# SAS_rev03.net
KiCad netlist of a schematic drawn in EAGLE
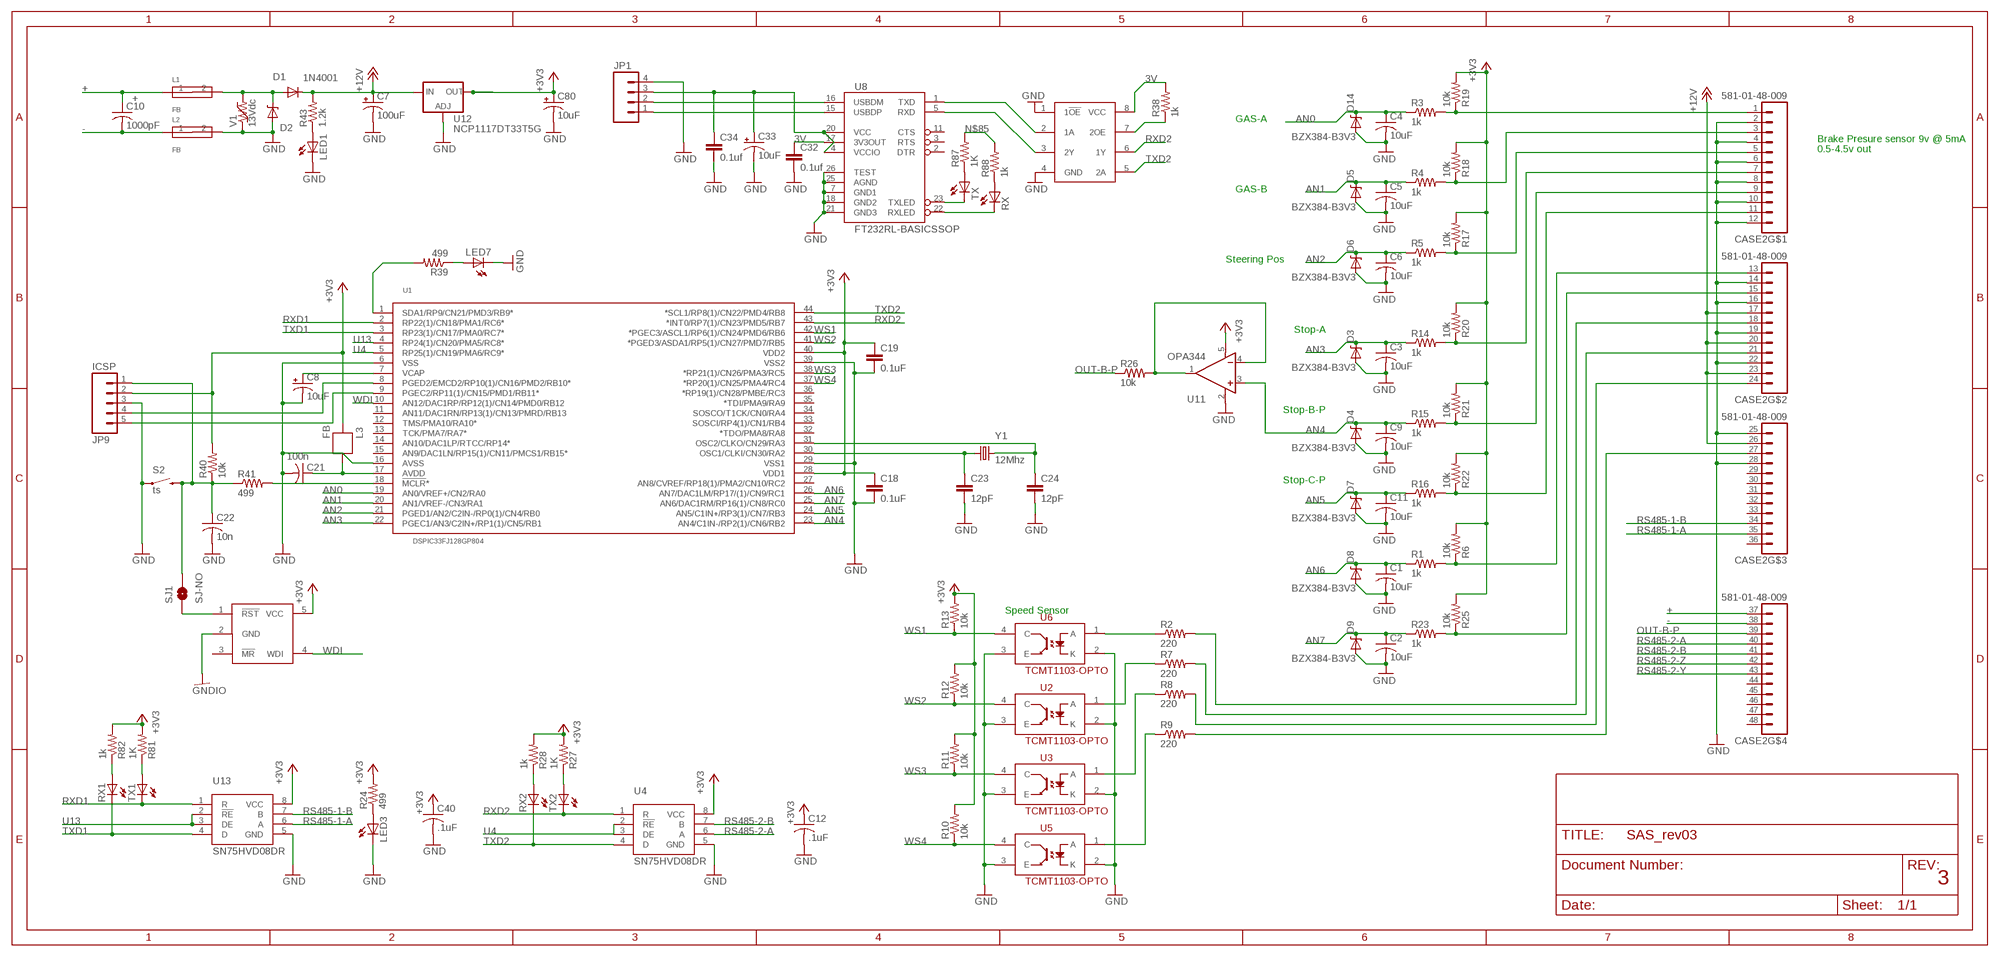
[diagram p0: schematic, sheet 1]

(export (version "E")
  (design (tool "Eeschema 10.0.6"))
  (components
    (comp (ref "C1")
      (value "10uF")
      (footprint "eagle-import:C0805")
      (libsource (lib "eagle-import") (part "C-USC0805"))
    )
    (comp (ref "C2")
      (value "10uF")
      (footprint "eagle-import:C0805")
      (libsource (lib "eagle-import") (part "C-USC0805"))
    )
    (comp (ref "C3")
      (value "10uF")
      (footprint "eagle-import:C0805")
      (libsource (lib "eagle-import") (part "C-USC0805"))
    )
    (comp (ref "C4")
      (value "10uF")
      (footprint "eagle-import:C0805")
      (libsource (lib "eagle-import") (part "C-USC0805"))
    )
    (comp (ref "C5")
      (value "10uF")
      (footprint "eagle-import:C0805")
      (libsource (lib "eagle-import") (part "C-USC0805"))
    )
    (comp (ref "C6")
      (value "10uF")
      (footprint "eagle-import:C0805")
      (libsource (lib "eagle-import") (part "C-USC0805"))
    )
    (comp (ref "C7")
      (value "100uF")
      (footprint "eagle-import:EIA7343")
      (libsource (lib "eagle-import") (part "SparkFun-Capacitors_CAP_POL7343"))
    )
    (comp (ref "C8")
      (value "10uF")
      (footprint "eagle-import:EIA3216")
      (libsource (lib "eagle-import") (part "10UF-TANT"))
    )
    (comp (ref "C9")
      (value "10uF")
      (footprint "eagle-import:C0805")
      (libsource (lib "eagle-import") (part "C-USC0805"))
    )
    (comp (ref "C10")
      (value "1000pF")
      (footprint "eagle-import:C1825")
      (libsource (lib "eagle-import") (part "C-USC1825"))
    )
    (comp (ref "C11")
      (value "10uF")
      (footprint "eagle-import:C0805")
      (libsource (lib "eagle-import") (part "C-USC0805"))
    )
    (comp (ref "C12")
      (value ".1uF")
      (footprint "eagle-import:C0805")
      (libsource (lib "eagle-import") (part "C-USC0805"))
    )
    (comp (ref "C18")
      (value "0.1uF")
      (footprint "eagle-import:0805")
      (libsource (lib "eagle-import") (part "SparkFun-Capacitors_CAP0805"))
    )
    (comp (ref "C19")
      (value "0.1uF")
      (footprint "eagle-import:0805")
      (libsource (lib "eagle-import") (part "SparkFun-Capacitors_CAP0805"))
    )
    (comp (ref "C21")
      (value "100n")
      (footprint "eagle-import:C0805")
      (libsource (lib "eagle-import") (part "C-USC0805"))
    )
    (comp (ref "C22")
      (value "10n")
      (footprint "eagle-import:C0805")
      (libsource (lib "eagle-import") (part "C-USC0805"))
    )
    (comp (ref "C23")
      (value "12pF")
      (footprint "eagle-import:0805")
      (libsource (lib "eagle-import") (part "SparkFun-Capacitors_CAP0805"))
    )
    (comp (ref "C24")
      (value "12pF")
      (footprint "eagle-import:0805")
      (libsource (lib "eagle-import") (part "SparkFun-Capacitors_CAP0805"))
    )
    (comp (ref "C32")
      (value "0.1uf")
      (footprint "eagle-import:0805")
      (libsource (lib "eagle-import") (part "CAP0805"))
    )
    (comp (ref "C33")
      (value "10uF")
      (footprint "eagle-import:EIA3216")
      (libsource (lib "eagle-import") (part "CAP_POL1206"))
    )
    (comp (ref "C34")
      (value "0.1uf")
      (footprint "eagle-import:0805")
      (libsource (lib "eagle-import") (part "CAP0805"))
    )
    (comp (ref "C40")
      (value ".1uF")
      (footprint "eagle-import:C0805")
      (libsource (lib "eagle-import") (part "C-USC0805"))
    )
    (comp (ref "C80")
      (value "10uF")
      (footprint "eagle-import:POLC1206")
      (libsource (lib "eagle-import") (part "POLCAP"))
    )
    (comp (ref "CASE2")
      (value "581-01-48-009")
      (footprint "eagle-import:581-01-48-009")
      (libsource (lib "eagle-import") (part "581-01-48-009"))
    )
    (comp (ref "D1")
      (value "1N4001")
      (footprint "eagle-import:SOD123")
      (libsource (lib "eagle-import") (part "DIODE-SOD123"))
    )
    (comp (ref "D2")
      (value "MM5Z30")
      (footprint "eagle-import:SOD-523F")
      (libsource (lib "eagle-import") (part "MM5Z30"))
    )
    (comp (ref "D3")
      (value "BZX384-B3V3")
      (footprint "eagle-import:SOD-323")
      (libsource (lib "eagle-import") (part "DIODE-ZENER-BZT52"))
    )
    (comp (ref "D4")
      (value "BZX384-B3V3")
      (footprint "eagle-import:SOD-323")
      (libsource (lib "eagle-import") (part "DIODE-ZENER-BZT52"))
    )
    (comp (ref "D5")
      (value "BZX384-B3V3")
      (footprint "eagle-import:SOD-323")
      (libsource (lib "eagle-import") (part "DIODE-ZENER-BZT52"))
    )
    (comp (ref "D6")
      (value "BZX384-B3V3")
      (footprint "eagle-import:SOD-323")
      (libsource (lib "eagle-import") (part "DIODE-ZENER-BZT52"))
    )
    (comp (ref "D7")
      (value "BZX384-B3V3")
      (footprint "eagle-import:SOD-323")
      (libsource (lib "eagle-import") (part "DIODE-ZENER-BZT52"))
    )
    (comp (ref "D8")
      (value "BZX384-B3V3")
      (footprint "eagle-import:SOD-323")
      (libsource (lib "eagle-import") (part "DIODE-ZENER-BZT52"))
    )
    (comp (ref "D9")
      (value "BZX384-B3V3")
      (footprint "eagle-import:SOD-323")
      (libsource (lib "eagle-import") (part "DIODE-ZENER-BZT52"))
    )
    (comp (ref "D14")
      (value "BZX384-B3V3")
      (footprint "eagle-import:SOD-323")
      (libsource (lib "eagle-import") (part "DIODE-ZENER-BZT52"))
    )
    (comp (ref "JP1")
      (value "M04POLAR")
      (footprint "eagle-import:MOLEX-1X4")
      (libsource (lib "eagle-import") (part "M04POLAR"))
    )
    (comp (ref "JP9")
      (value "ICSP")
      (footprint "eagle-import:1X05_LOCK_LONGPADS")
      (libsource (lib "eagle-import") (part "M05LOCK_LONGPADS"))
    )
    (comp (ref "L1")
      (value "FB")
      (footprint "eagle-import:0603")
      (libsource (lib "eagle-import") (part "FERITEBEAD"))
    )
    (comp (ref "L2")
      (value "FB")
      (footprint "eagle-import:0603")
      (libsource (lib "eagle-import") (part "FERITEBEAD"))
    )
    (comp (ref "L3")
      (value "FB")
      (footprint "eagle-import:0603")
      (libsource (lib "eagle-import") (part "FB"))
    )
    (comp (ref "LED1")
      (value "LEDCHIP-LED0805")
      (footprint "eagle-import:CHIP-LED0805")
      (libsource (lib "eagle-import") (part "LEDCHIP-LED0805"))
    )
    (comp (ref "LED3")
      (value "LEDCHIP-LED0805")
      (footprint "eagle-import:CHIP-LED0805")
      (libsource (lib "eagle-import") (part "LEDCHIP-LED0805"))
    )
    (comp (ref "LED7")
      (value "LEDCHIP-LED0805")
      (footprint "eagle-import:CHIP-LED0805")
      (libsource (lib "eagle-import") (part "LEDCHIP-LED0805"))
    )
    (comp (ref "R1")
      (value "1k")
      (footprint "eagle-import:R0805")
      (libsource (lib "eagle-import") (part "R-US_R0805"))
    )
    (comp (ref "R2")
      (value "220")
      (footprint "eagle-import:R0805")
      (libsource (lib "eagle-import") (part "R-US_R0805"))
    )
    (comp (ref "R3")
      (value "1k")
      (footprint "eagle-import:R0805")
      (libsource (lib "eagle-import") (part "R-US_R0805"))
    )
    (comp (ref "R4")
      (value "1k")
      (footprint "eagle-import:R0805")
      (libsource (lib "eagle-import") (part "R-US_R0805"))
    )
    (comp (ref "R5")
      (value "1k")
      (footprint "eagle-import:R0805")
      (libsource (lib "eagle-import") (part "R-US_R0805"))
    )
    (comp (ref "R6")
      (value "10k")
      (footprint "eagle-import:R0805")
      (libsource (lib "eagle-import") (part "R-US_R0805"))
    )
    (comp (ref "R7")
      (value "220")
      (footprint "eagle-import:R0805")
      (libsource (lib "eagle-import") (part "R-US_R0805"))
    )
    (comp (ref "R8")
      (value "220")
      (footprint "eagle-import:R0805")
      (libsource (lib "eagle-import") (part "R-US_R0805"))
    )
    (comp (ref "R9")
      (value "220")
      (footprint "eagle-import:R0805")
      (libsource (lib "eagle-import") (part "R-US_R0805"))
    )
    (comp (ref "R10")
      (value "10k")
      (footprint "eagle-import:R0805")
      (libsource (lib "eagle-import") (part "R-US_R0805"))
    )
    (comp (ref "R11")
      (value "10k")
      (footprint "eagle-import:R0805")
      (libsource (lib "eagle-import") (part "R-US_R0805"))
    )
    (comp (ref "R12")
      (value "10k")
      (footprint "eagle-import:R0805")
      (libsource (lib "eagle-import") (part "R-US_R0805"))
    )
    (comp (ref "R13")
      (value "10k")
      (footprint "eagle-import:R0805")
      (libsource (lib "eagle-import") (part "R-US_R0805"))
    )
    (comp (ref "R14")
      (value "1k")
      (footprint "eagle-import:R0805")
      (libsource (lib "eagle-import") (part "R-US_R0805"))
    )
    (comp (ref "R15")
      (value "1k")
      (footprint "eagle-import:R0805")
      (libsource (lib "eagle-import") (part "R-US_R0805"))
    )
    (comp (ref "R16")
      (value "1k")
      (footprint "eagle-import:R0805")
      (libsource (lib "eagle-import") (part "R-US_R0805"))
    )
    (comp (ref "R17")
      (value "10k")
      (footprint "eagle-import:R0805")
      (libsource (lib "eagle-import") (part "R-US_R0805"))
    )
    (comp (ref "R18")
      (value "10k")
      (footprint "eagle-import:R0805")
      (libsource (lib "eagle-import") (part "R-US_R0805"))
    )
    (comp (ref "R19")
      (value "10k")
      (footprint "eagle-import:R0805")
      (libsource (lib "eagle-import") (part "R-US_R0805"))
    )
    (comp (ref "R20")
      (value "10k")
      (footprint "eagle-import:R0805")
      (libsource (lib "eagle-import") (part "R-US_R0805"))
    )
    (comp (ref "R21")
      (value "10k")
      (footprint "eagle-import:R0805")
      (libsource (lib "eagle-import") (part "R-US_R0805"))
    )
    (comp (ref "R22")
      (value "10k")
      (footprint "eagle-import:R0805")
      (libsource (lib "eagle-import") (part "R-US_R0805"))
    )
    (comp (ref "R23")
      (value "1k")
      (footprint "eagle-import:R0805")
      (libsource (lib "eagle-import") (part "R-US_R0805"))
    )
    (comp (ref "R24")
      (value "499")
      (footprint "eagle-import:R0805")
      (libsource (lib "eagle-import") (part "R-US_R0805"))
    )
    (comp (ref "R25")
      (value "10k")
      (footprint "eagle-import:R0805")
      (libsource (lib "eagle-import") (part "R-US_R0805"))
    )
    (comp (ref "R26")
      (value "10k")
      (footprint "eagle-import:R0805")
      (libsource (lib "eagle-import") (part "R-US_R0805"))
    )
    (comp (ref "R27")
      (value "1K")
      (footprint "eagle-import:R0805")
      (libsource (lib "eagle-import") (part "R-US_R0805"))
    )
    (comp (ref "R28")
      (value "1k")
      (footprint "eagle-import:R0805")
      (libsource (lib "eagle-import") (part "R-US_R0805"))
    )
    (comp (ref "R38")
      (value "1k")
      (footprint "eagle-import:R0805")
      (libsource (lib "eagle-import") (part "R-US_R0805"))
    )
    (comp (ref "R39")
      (value "499")
      (footprint "eagle-import:0805")
      (libsource (lib "eagle-import") (part "RESISTOR0805-RES"))
    )
    (comp (ref "R40")
      (value "10k")
      (footprint "eagle-import:0805")
      (libsource (lib "eagle-import") (part "RESISTOR0805-RES"))
    )
    (comp (ref "R41")
      (value "499")
      (footprint "eagle-import:0805")
      (libsource (lib "eagle-import") (part "SparkFun-Resistors_RESISTOR0805-RES"))
    )
    (comp (ref "R43")
      (value "1.2k")
      (footprint "eagle-import:R0805")
      (libsource (lib "eagle-import") (part "R-US_R0805"))
    )
    (comp (ref "R81")
      (value "1K")
      (footprint "eagle-import:R0805")
      (libsource (lib "eagle-import") (part "R-US_R0805"))
    )
    (comp (ref "R82")
      (value "1k")
      (footprint "eagle-import:R0805")
      (libsource (lib "eagle-import") (part "R-US_R0805"))
    )
    (comp (ref "R87")
      (value "1K")
      (footprint "eagle-import:R0805")
      (libsource (lib "eagle-import") (part "R-US_R0805"))
    )
    (comp (ref "R88")
      (value "1k")
      (footprint "eagle-import:R0805")
      (libsource (lib "eagle-import") (part "R-US_R0805"))
    )
    (comp (ref "RX")
      (value "LEDCHIPLED_0805")
      (footprint "eagle-import:CHIPLED_0805")
      (libsource (lib "eagle-import") (part "LEDCHIPLED_0805"))
    )
    (comp (ref "RX1")
      (value "LEDCHIPLED_0805")
      (footprint "eagle-import:CHIPLED_0805")
      (libsource (lib "eagle-import") (part "LEDCHIPLED_0805"))
    )
    (comp (ref "RX2")
      (value "LEDCHIPLED_0805")
      (footprint "eagle-import:CHIPLED_0805")
      (libsource (lib "eagle-import") (part "LEDCHIPLED_0805"))
    )
    (comp (ref "S2")
      (value "ts")
      (footprint "eagle-import:TACTILE-PTH")
      (libsource (lib "eagle-import") (part "SWITCH-MOMENTARY-2PTH"))
    )
    (comp (ref "SJ1")
      (value "SJ-NO")
      (footprint "eagle-import:SJ_2S-NO")
      (libsource (lib "eagle-import") (part "SOLDERJUMPERNO"))
    )
    (comp (ref "TX")
      (value "LEDCHIPLED_0805")
      (footprint "eagle-import:CHIPLED_0805")
      (libsource (lib "eagle-import") (part "LEDCHIPLED_0805"))
    )
    (comp (ref "TX1")
      (value "LEDCHIPLED_0805")
      (footprint "eagle-import:CHIPLED_0805")
      (libsource (lib "eagle-import") (part "LEDCHIPLED_0805"))
    )
    (comp (ref "TX2")
      (value "LEDCHIPLED_0805")
      (footprint "eagle-import:CHIPLED_0805")
      (libsource (lib "eagle-import") (part "LEDCHIPLED_0805"))
    )
    (comp (ref "U1")
      (value "DSPIC33FJ128GP804")
      (footprint "eagle-import:TQFP-44")
      (libsource (lib "eagle-import") (part "DSPIC33FJ128GP804"))
    )
    (comp (ref "U2")
      (value "TCMT1103-OPTO")
      (footprint "eagle-import:SSOP-4")
      (libsource (lib "eagle-import") (part "TCMT1103-OPTO"))
    )
    (comp (ref "U3")
      (value "TCMT1103-OPTO")
      (footprint "eagle-import:SSOP-4")
      (libsource (lib "eagle-import") (part "TCMT1103-OPTO"))
    )
    (comp (ref "U4")
      (value "SN75HVD08DR")
      (footprint "eagle-import:SO-8")
      (libsource (lib "eagle-import") (part "SN75HVD08DR"))
    )
    (comp (ref "U5")
      (value "TCMT1103-OPTO")
      (footprint "eagle-import:SSOP-4")
      (libsource (lib "eagle-import") (part "TCMT1103-OPTO"))
    )
    (comp (ref "U6")
      (value "TCMT1103-OPTO")
      (footprint "eagle-import:SSOP-4")
      (libsource (lib "eagle-import") (part "TCMT1103-OPTO"))
    )
    (comp (ref "U8")
      (value "FT232RL-BASICSSOP")
      (footprint "eagle-import:SSOP28DB")
      (libsource (lib "eagle-import") (part "FT232RL-BASICSSOP"))
    )
    (comp (ref "U9")
      (value "MAX823")
      (footprint "eagle-import:SOT23-5L")
      (libsource (lib "eagle-import") (part "MAX823"))
    )
    (comp (ref "U11")
      (value "OPA344")
      (footprint "eagle-import:SOT23-5")
      (libsource (lib "eagle-import") (part "OPA344"))
    )
    (comp (ref "U12")
      (value "NCP1117DT33T5G")
      (footprint "eagle-import:V-REG_DPACK")
      (libsource (lib "eagle-import") (part "V_REG_317DPACK"))
    )
    (comp (ref "U13")
      (value "SN75HVD08DR")
      (footprint "eagle-import:SO-8")
      (libsource (lib "eagle-import") (part "SN75HVD08DR"))
    )
    (comp (ref "U14")
      (value "SN74LVC2G241DCTR")
      (footprint "eagle-import:VFSOP-8")
      (libsource (lib "eagle-import") (part "SN74LVC2G241DCTR"))
    )
    (comp (ref "V1")
      (value "13Vdc")
      (footprint "eagle-import:0603")
      (libsource (lib "eagle-import") (part "VAR-RES"))
    )
    (comp (ref "Y1")
      (value "12Mhz")
      (footprint "eagle-import:CRYSTAL-SMD-5X3")
      (libsource (lib "eagle-import") (part "CRYSTAL5X3"))
    )
  )
  (nets
    (net (code "1") (name "+3V3") (class "Default")
      (node (ref "C12") (pin "1") (pinfunction "1_1") (pintype "passive"))
      (node (ref "C18") (pin "1") (pinfunction "1_1") (pintype "passive"))
      (node (ref "C19") (pin "1") (pinfunction "1_1") (pintype "passive"))
      (node (ref "C40") (pin "1") (pinfunction "1_1") (pintype "passive"))
      (node (ref "C80") (pin "1") (pinfunction "+_1") (pintype "passive"))
      (node (ref "JP9") (pin "2") (pinfunction "2_2") (pintype "passive"))
      (node (ref "L3") (pin "2") (pinfunction "P$2_2") (pintype "bidirectional"))
      (node (ref "R10") (pin "2") (pinfunction "2_2") (pintype "passive"))
      (node (ref "R11") (pin "2") (pinfunction "2_2") (pintype "passive"))
      (node (ref "R12") (pin "2") (pinfunction "2_2") (pintype "passive"))
      (node (ref "R13") (pin "2") (pinfunction "2_2") (pintype "passive"))
      (node (ref "R17") (pin "2") (pinfunction "2_2") (pintype "passive"))
      (node (ref "R18") (pin "2") (pinfunction "2_2") (pintype "passive"))
      (node (ref "R19") (pin "2") (pinfunction "2_2") (pintype "passive"))
      (node (ref "R20") (pin "2") (pinfunction "2_2") (pintype "passive"))
      (node (ref "R21") (pin "2") (pinfunction "2_2") (pintype "passive"))
      (node (ref "R22") (pin "2") (pinfunction "2_2") (pintype "passive"))
      (node (ref "R24") (pin "2") (pinfunction "2_2") (pintype "passive"))
      (node (ref "R25") (pin "2") (pinfunction "2_2") (pintype "passive"))
      (node (ref "R27") (pin "2") (pinfunction "2_2") (pintype "passive"))
      (node (ref "R28") (pin "2") (pinfunction "2_2") (pintype "passive"))
      (node (ref "R40") (pin "2") (pinfunction "2_2") (pintype "passive"))
      (node (ref "R6") (pin "2") (pinfunction "2_2") (pintype "passive"))
      (node (ref "R81") (pin "2") (pinfunction "2_2") (pintype "passive"))
      (node (ref "R82") (pin "2") (pinfunction "2_2") (pintype "passive"))
      (node (ref "U1") (pin "28") (pinfunction "VDD1_28") (pintype "bidirectional"))
      (node (ref "U1") (pin "40") (pinfunction "VDD2_40") (pintype "bidirectional"))
      (node (ref "U11") (pin "5") (pinfunction "V+_5") (pintype "power_in"))
      (node (ref "U12") (pin "4") (pinfunction "OUT_4") (pintype "output"))
      (node (ref "U13") (pin "8") (pinfunction "VCC_8") (pintype "bidirectional"))
      (node (ref "U4") (pin "8") (pinfunction "VCC_8") (pintype "bidirectional"))
      (node (ref "U9") (pin "5") (pinfunction "VCC_5") (pintype "bidirectional"))
    )
    (net (code "2") (name "+12V") (class "Default")
      (node (ref "C7") (pin "A") (pinfunction "+_A") (pintype "passive"))
      (node (ref "CASE2") (pin "17") (pinfunction "5_17") (pintype "passive"))
      (node (ref "CASE2") (pin "20") (pinfunction "8_20") (pintype "passive"))
      (node (ref "CASE2") (pin "23") (pinfunction "11_23") (pintype "passive"))
      (node (ref "CASE2") (pin "26") (pinfunction "2_26") (pintype "passive"))
      (node (ref "D1") (pin "C") (pinfunction "C_C") (pintype "passive"))
      (node (ref "R43") (pin "2") (pinfunction "2_2") (pintype "passive"))
      (node (ref "U12") (pin "3") (pinfunction "IN_3") (pintype "input"))
    )
    (net (code "3") (name "/+") (class "Default")
      (node (ref "C10") (pin "1") (pinfunction "1_1") (pintype "passive"))
      (node (ref "CASE2") (pin "37") (pinfunction "1_37") (pintype "passive"))
      (node (ref "L1") (pin "1") (pinfunction "P$1_1") (pintype "bidirectional"))
    )
    (net (code "4") (name "/-") (class "Default")
      (node (ref "C10") (pin "2") (pinfunction "2_2") (pintype "passive"))
      (node (ref "CASE2") (pin "38") (pinfunction "2_38") (pintype "passive"))
      (node (ref "L2") (pin "1") (pinfunction "P$1_1") (pintype "bidirectional"))
    )
    (net (code "5") (name "/3V") (class "Default")
      (node (ref "C32") (pin "1") (pinfunction "1_1") (pintype "passive"))
      (node (ref "R38") (pin "2") (pinfunction "2_2") (pintype "passive"))
      (node (ref "U14") (pin "8") (pinfunction "VCC_8") (pintype "bidirectional"))
      (node (ref "U8") (pin "17") (pinfunction "3V3OUT_17") (pintype "output"))
    )
    (net (code "6") (name "/AN0") (class "Default")
      (node (ref "C4") (pin "1") (pinfunction "1_1") (pintype "passive"))
      (node (ref "D14") (pin "1") (pinfunction "C_1") (pintype "passive"))
      (node (ref "R3") (pin "1") (pinfunction "1_1") (pintype "passive"))
      (node (ref "U1") (pin "19") (pinfunction "AN0/VREF+/CN2/RA0_19") (pintype "bidirectional"))
    )
    (net (code "7") (name "/AN1") (class "Default")
      (node (ref "C5") (pin "1") (pinfunction "1_1") (pintype "passive"))
      (node (ref "D5") (pin "1") (pinfunction "C_1") (pintype "passive"))
      (node (ref "R4") (pin "1") (pinfunction "1_1") (pintype "passive"))
      (node (ref "U1") (pin "20") (pinfunction "AN1/VREF-/CN3/RA1_20") (pintype "bidirectional"))
    )
    (net (code "8") (name "/AN2") (class "Default")
      (node (ref "C6") (pin "1") (pinfunction "1_1") (pintype "passive"))
      (node (ref "D6") (pin "1") (pinfunction "C_1") (pintype "passive"))
      (node (ref "R5") (pin "1") (pinfunction "1_1") (pintype "passive"))
      (node (ref "U1") (pin "21") (pinfunction "PGED1/AN2/C2IN-/RP0(1)/CN4/RB0_21") (pintype "bidirectional"))
    )
    (net (code "9") (name "/AN3") (class "Default")
      (node (ref "C3") (pin "1") (pinfunction "1_1") (pintype "passive"))
      (node (ref "D3") (pin "1") (pinfunction "C_1") (pintype "passive"))
      (node (ref "R14") (pin "1") (pinfunction "1_1") (pintype "passive"))
      (node (ref "U1") (pin "22") (pinfunction "PGEC1/AN3/C2IN+/RP1(1)/CN5/RB1_22") (pintype "bidirectional"))
    )
    (net (code "10") (name "/AN4") (class "Default")
      (node (ref "C9") (pin "1") (pinfunction "1_1") (pintype "passive"))
      (node (ref "D4") (pin "1") (pinfunction "C_1") (pintype "passive"))
      (node (ref "R15") (pin "1") (pinfunction "1_1") (pintype "passive"))
      (node (ref "U1") (pin "23") (pinfunction "AN4/C1IN-/RP2(1)/CN6/RB2_23") (pintype "bidirectional"))
      (node (ref "U11") (pin "3") (pinfunction "+IN_3") (pintype "input"))
    )
    (net (code "11") (name "/AN5") (class "Default")
      (node (ref "C11") (pin "1") (pinfunction "1_1") (pintype "passive"))
      (node (ref "D7") (pin "1") (pinfunction "C_1") (pintype "passive"))
      (node (ref "R16") (pin "1") (pinfunction "1_1") (pintype "passive"))
      (node (ref "U1") (pin "24") (pinfunction "AN5/C1IN+/RP3(1)/CN7/RB3_24") (pintype "bidirectional"))
    )
    (net (code "12") (name "/AN6") (class "Default")
      (node (ref "C1") (pin "1") (pinfunction "1_1") (pintype "passive"))
      (node (ref "D8") (pin "1") (pinfunction "C_1") (pintype "passive"))
      (node (ref "R1") (pin "1") (pinfunction "1_1") (pintype "passive"))
      (node (ref "U1") (pin "26") (pinfunction "AN7/DAC1LM/RP17/(1)/CN9/RC1_26") (pintype "bidirectional"))
    )
    (net (code "13") (name "/AN7") (class "Default")
      (node (ref "C2") (pin "1") (pinfunction "1_1") (pintype "passive"))
      (node (ref "D9") (pin "1") (pinfunction "C_1") (pintype "passive"))
      (node (ref "R23") (pin "1") (pinfunction "1_1") (pintype "passive"))
      (node (ref "U1") (pin "25") (pinfunction "AN6/DAC1RM/RP16(1)/CN8/RC0_25") (pintype "bidirectional"))
    )
    (net (code "14") (name "/N$85") (class "Default")
      (node (ref "C33") (pin "A") (pinfunction "+_A") (pintype "passive"))
      (node (ref "C34") (pin "1") (pinfunction "1_1") (pintype "passive"))
      (node (ref "JP1") (pin "3") (pinfunction "3_3") (pintype "passive"))
      (node (ref "R87") (pin "2") (pinfunction "2_2") (pintype "passive"))
      (node (ref "R88") (pin "2") (pinfunction "2_2") (pintype "passive"))
      (node (ref "U8") (pin "20") (pinfunction "VCC_20") (pintype "power_in"))
      (node (ref "U8") (pin "4") (pinfunction "VCCIO_4") (pintype "power_in"))
    )
    (net (code "15") (name "/OUT-B-P") (class "Default")
      (node (ref "CASE2") (pin "39") (pinfunction "3_39") (pintype "passive"))
      (node (ref "R26") (pin "1") (pinfunction "1_1") (pintype "passive"))
    )
    (net (code "16") (name "/RS485-1-A") (class "Default")
      (node (ref "CASE2") (pin "35") (pinfunction "11_35") (pintype "passive"))
      (node (ref "U13") (pin "6") (pinfunction "A_6") (pintype "bidirectional"))
    )
    (net (code "17") (name "/RS485-1-B") (class "Default")
      (node (ref "CASE2") (pin "34") (pinfunction "10_34") (pintype "passive"))
      (node (ref "U13") (pin "7") (pinfunction "B_7") (pintype "bidirectional"))
    )
    (net (code "18") (name "/RS485-2-A") (class "Default")
      (node (ref "CASE2") (pin "40") (pinfunction "4_40") (pintype "passive"))
      (node (ref "U4") (pin "6") (pinfunction "A_6") (pintype "bidirectional"))
    )
    (net (code "19") (name "/RS485-2-B") (class "Default")
      (node (ref "CASE2") (pin "41") (pinfunction "5_41") (pintype "passive"))
      (node (ref "U4") (pin "7") (pinfunction "B_7") (pintype "bidirectional"))
    )
    (net (code "20") (name "/RS485-2-Y") (class "Default")
      (node (ref "CASE2") (pin "43") (pinfunction "7_43") (pintype "passive"))
    )
    (net (code "21") (name "/RS485-2-Z") (class "Default")
      (node (ref "CASE2") (pin "42") (pinfunction "6_42") (pintype "passive"))
    )
    (net (code "22") (name "/RXD1") (class "Default")
      (node (ref "TX1") (pin "C") (pinfunction "C_C") (pintype "passive"))
      (node (ref "U1") (pin "2") (pinfunction "RP22(1)/CN18/PMA1/RC6*_2") (pintype "bidirectional"))
      (node (ref "U13") (pin "1") (pinfunction "R_1") (pintype "bidirectional"))
    )
    (net (code "23") (name "/RXD2") (class "Default")
      (node (ref "TX2") (pin "C") (pinfunction "C_C") (pintype "passive"))
      (node (ref "U1") (pin "43") (pinfunction "*INT0/RP7(1)/CN23/PMD5/RB7_43") (pintype "bidirectional"))
      (node (ref "U14") (pin "6") (pinfunction "1Y_6") (pintype "bidirectional"))
      (node (ref "U4") (pin "1") (pinfunction "R_1") (pintype "bidirectional"))
    )
    (net (code "24") (name "/TXD1") (class "Default")
      (node (ref "RX1") (pin "C") (pinfunction "C_C") (pintype "passive"))
      (node (ref "U1") (pin "3") (pinfunction "RP23(1)/CN17/PMA0/RC7*_3") (pintype "bidirectional"))
      (node (ref "U13") (pin "4") (pinfunction "D_4") (pintype "bidirectional"))
    )
    (net (code "25") (name "/TXD2") (class "Default")
      (node (ref "RX2") (pin "C") (pinfunction "C_C") (pintype "passive"))
      (node (ref "U1") (pin "44") (pinfunction "*SCL1/RP8(1)/CN22/PMD4/RB8_44") (pintype "bidirectional"))
      (node (ref "U14") (pin "5") (pinfunction "2A_5") (pintype "bidirectional"))
      (node (ref "U4") (pin "4") (pinfunction "D_4") (pintype "bidirectional"))
    )
    (net (code "26") (name "/U4") (class "Default")
      (node (ref "U1") (pin "5") (pinfunction "RP25(1)/CN19/PMA6/RC9*_5") (pintype "bidirectional"))
      (node (ref "U4") (pin "2") (pinfunction "~{RE}_2") (pintype "bidirectional"))
      (node (ref "U4") (pin "3") (pinfunction "DE_3") (pintype "bidirectional"))
    )
    (net (code "27") (name "/U13") (class "Default")
      (node (ref "U1") (pin "4") (pinfunction "RP24(1)/CN20/PMA5/RC8*_4") (pintype "bidirectional"))
      (node (ref "U13") (pin "2") (pinfunction "~{RE}_2") (pintype "bidirectional"))
      (node (ref "U13") (pin "3") (pinfunction "DE_3") (pintype "bidirectional"))
    )
    (net (code "28") (name "/WDI") (class "Default")
      (node (ref "U1") (pin "10") (pinfunction "AN12/DAC1RP/RP12(1)/CN14/PMD0/RB12_10") (pintype "bidirectional"))
      (node (ref "U9") (pin "4") (pinfunction "WDI_4") (pintype "bidirectional"))
    )
    (net (code "29") (name "/WS1") (class "Default")
      (node (ref "R13") (pin "1") (pinfunction "1_1") (pintype "passive"))
      (node (ref "U1") (pin "42") (pinfunction "*PGEC3/ASCL1/RP6(1)/CN24/PMD6/RB6_42") (pintype "bidirectional"))
      (node (ref "U6") (pin "4") (pinfunction "C_4") (pintype "bidirectional"))
    )
    (net (code "30") (name "/WS2") (class "Default")
      (node (ref "R12") (pin "1") (pinfunction "1_1") (pintype "passive"))
      (node (ref "U1") (pin "41") (pinfunction "*PGED3/ASDA1/RP5(1)/CN27/PMD7/RB5_41") (pintype "bidirectional"))
      (node (ref "U2") (pin "4") (pinfunction "C_4") (pintype "bidirectional"))
    )
    (net (code "31") (name "/WS3") (class "Default")
      (node (ref "R11") (pin "1") (pinfunction "1_1") (pintype "passive"))
      (node (ref "U1") (pin "38") (pinfunction "*RP21(1)/CN26/PMA3/RC5_38") (pintype "bidirectional"))
      (node (ref "U3") (pin "4") (pinfunction "C_4") (pintype "bidirectional"))
    )
    (net (code "32") (name "/WS4") (class "Default")
      (node (ref "R10") (pin "1") (pinfunction "1_1") (pintype "passive"))
      (node (ref "U1") (pin "37") (pinfunction "*RP20(1)/CN25/PMA4/RC4_37") (pintype "bidirectional"))
      (node (ref "U5") (pin "4") (pinfunction "C_4") (pintype "bidirectional"))
    )
    (net (code "33") (name "GND") (class "Default")
      (node (ref "C1") (pin "2") (pinfunction "2_2") (pintype "passive"))
      (node (ref "C11") (pin "2") (pinfunction "2_2") (pintype "passive"))
      (node (ref "C12") (pin "2") (pinfunction "2_2") (pintype "passive"))
      (node (ref "C18") (pin "2") (pinfunction "2_2") (pintype "passive"))
      (node (ref "C19") (pin "2") (pinfunction "2_2") (pintype "passive"))
      (node (ref "C2") (pin "2") (pinfunction "2_2") (pintype "passive"))
      (node (ref "C21") (pin "2") (pinfunction "2_2") (pintype "passive"))
      (node (ref "C22") (pin "2") (pinfunction "2_2") (pintype "passive"))
      (node (ref "C23") (pin "2") (pinfunction "2_2") (pintype "passive"))
      (node (ref "C24") (pin "2") (pinfunction "2_2") (pintype "passive"))
      (node (ref "C3") (pin "2") (pinfunction "2_2") (pintype "passive"))
      (node (ref "C32") (pin "2") (pinfunction "2_2") (pintype "passive"))
      (node (ref "C33") (pin "C") (pinfunction "-_C") (pintype "passive"))
      (node (ref "C34") (pin "2") (pinfunction "2_2") (pintype "passive"))
      (node (ref "C4") (pin "2") (pinfunction "2_2") (pintype "passive"))
      (node (ref "C40") (pin "2") (pinfunction "2_2") (pintype "passive"))
      (node (ref "C5") (pin "2") (pinfunction "2_2") (pintype "passive"))
      (node (ref "C6") (pin "2") (pinfunction "2_2") (pintype "passive"))
      (node (ref "C7") (pin "C") (pinfunction "-_C") (pintype "passive"))
      (node (ref "C8") (pin "C") (pinfunction "-_C") (pintype "passive"))
      (node (ref "C80") (pin "2") (pinfunction "-_2") (pintype "passive"))
      (node (ref "C9") (pin "2") (pinfunction "2_2") (pintype "passive"))
      (node (ref "CASE2") (pin "10") (pinfunction "10_10") (pintype "passive"))
      (node (ref "CASE2") (pin "12") (pinfunction "12_12") (pintype "passive"))
      (node (ref "CASE2") (pin "14") (pinfunction "2_14") (pintype "passive"))
      (node (ref "CASE2") (pin "16") (pinfunction "4_16") (pintype "passive"))
      (node (ref "CASE2") (pin "19") (pinfunction "7_19") (pintype "passive"))
      (node (ref "CASE2") (pin "2") (pinfunction "2_2") (pintype "passive"))
      (node (ref "CASE2") (pin "22") (pinfunction "10_22") (pintype "passive"))
      (node (ref "CASE2") (pin "25") (pinfunction "1_25") (pintype "passive"))
      (node (ref "CASE2") (pin "28") (pinfunction "4_28") (pintype "passive"))
      (node (ref "CASE2") (pin "4") (pinfunction "4_4") (pintype "passive"))
      (node (ref "CASE2") (pin "6") (pinfunction "6_6") (pintype "passive"))
      (node (ref "CASE2") (pin "8") (pinfunction "8_8") (pintype "passive"))
      (node (ref "D14") (pin "2") (pinfunction "A_2") (pintype "passive"))
      (node (ref "D2") (pin "A") (pinfunction "A_A") (pintype "passive"))
      (node (ref "D3") (pin "2") (pinfunction "A_2") (pintype "passive"))
      (node (ref "D4") (pin "2") (pinfunction "A_2") (pintype "passive"))
      (node (ref "D5") (pin "2") (pinfunction "A_2") (pintype "passive"))
      (node (ref "D6") (pin "2") (pinfunction "A_2") (pintype "passive"))
      (node (ref "D7") (pin "2") (pinfunction "A_2") (pintype "passive"))
      (node (ref "D8") (pin "2") (pinfunction "A_2") (pintype "passive"))
      (node (ref "D9") (pin "2") (pinfunction "A_2") (pintype "passive"))
      (node (ref "JP1") (pin "4") (pinfunction "4_4") (pintype "passive"))
      (node (ref "JP9") (pin "3") (pinfunction "3_3") (pintype "passive"))
      (node (ref "L2") (pin "2") (pinfunction "P$2_2") (pintype "bidirectional"))
      (node (ref "LED1") (pin "C") (pinfunction "C_C") (pintype "passive"))
      (node (ref "LED3") (pin "C") (pinfunction "C_C") (pintype "passive"))
      (node (ref "LED7") (pin "C") (pinfunction "C_C") (pintype "passive"))
      (node (ref "S2") (pin "1") (pinfunction "1_1") (pintype "passive"))
      (node (ref "U1") (pin "16") (pinfunction "AVSS_16") (pintype "bidirectional"))
      (node (ref "U1") (pin "29") (pinfunction "VSS1_29") (pintype "bidirectional"))
      (node (ref "U1") (pin "39") (pinfunction "VSS2_39") (pintype "bidirectional"))
      (node (ref "U1") (pin "6") (pinfunction "VSS_6") (pintype "bidirectional"))
      (node (ref "U11") (pin "2") (pinfunction "V-_2") (pintype "power_in"))
      (node (ref "U12") (pin "1") (pinfunction "ADJ_1") (pintype "input"))
      (node (ref "U13") (pin "5") (pinfunction "GND_5") (pintype "bidirectional"))
      (node (ref "U14") (pin "1") (pinfunction "1~{OE}_1") (pintype "bidirectional"))
      (node (ref "U14") (pin "4") (pinfunction "GND_4") (pintype "bidirectional"))
      (node (ref "U2") (pin "2") (pinfunction "K_2") (pintype "bidirectional"))
      (node (ref "U2") (pin "3") (pinfunction "E_3") (pintype "bidirectional"))
      (node (ref "U3") (pin "2") (pinfunction "K_2") (pintype "bidirectional"))
      (node (ref "U3") (pin "3") (pinfunction "E_3") (pintype "bidirectional"))
      (node (ref "U4") (pin "5") (pinfunction "GND_5") (pintype "bidirectional"))
      (node (ref "U5") (pin "2") (pinfunction "K_2") (pintype "bidirectional"))
      (node (ref "U5") (pin "3") (pinfunction "E_3") (pintype "bidirectional"))
      (node (ref "U6") (pin "2") (pinfunction "K_2") (pintype "bidirectional"))
      (node (ref "U6") (pin "3") (pinfunction "E_3") (pintype "bidirectional"))
      (node (ref "U8") (pin "18") (pinfunction "GND2_18") (pintype "power_in"))
      (node (ref "U8") (pin "21") (pinfunction "GND3_21") (pintype "power_in"))
      (node (ref "U8") (pin "25") (pinfunction "AGND_25") (pintype "power_in"))
      (node (ref "U8") (pin "26") (pinfunction "TEST_26") (pintype "input"))
      (node (ref "U8") (pin "7") (pinfunction "GND1_7") (pintype "power_in"))
      (node (ref "V1") (pin "1") (pinfunction "1_1") (pintype "passive"))
    )
    (net (code "34") (name "GNDIO") (class "Default")
      (node (ref "U9") (pin "2") (pinfunction "GND_2") (pintype "bidirectional"))
    )
    (net (code "35") (name "Net-(C8-+)") (class "Default")
      (node (ref "C8") (pin "A") (pinfunction "+_A") (pintype "passive"))
      (node (ref "U1") (pin "7") (pinfunction "VCAP_7") (pintype "bidirectional"))
    )
    (net (code "36") (name "Net-(CASE2-Pad1)") (class "Default")
      (node (ref "CASE2") (pin "1") (pinfunction "1_1") (pintype "passive"))
      (node (ref "R19") (pin "1") (pinfunction "1_1") (pintype "passive"))
      (node (ref "R3") (pin "2") (pinfunction "2_2") (pintype "passive"))
    )
    (net (code "37") (name "Net-(CASE2-Pad3)") (class "Default")
      (node (ref "CASE2") (pin "3") (pinfunction "3_3") (pintype "passive"))
      (node (ref "R18") (pin "1") (pinfunction "1_1") (pintype "passive"))
      (node (ref "R4") (pin "2") (pinfunction "2_2") (pintype "passive"))
    )
    (net (code "38") (name "Net-(CASE2-Pad5)") (class "Default")
      (node (ref "CASE2") (pin "5") (pinfunction "5_5") (pintype "passive"))
      (node (ref "R17") (pin "1") (pinfunction "1_1") (pintype "passive"))
      (node (ref "R5") (pin "2") (pinfunction "2_2") (pintype "passive"))
    )
    (net (code "39") (name "Net-(CASE2-Pad7)") (class "Default")
      (node (ref "CASE2") (pin "7") (pinfunction "7_7") (pintype "passive"))
      (node (ref "R14") (pin "2") (pinfunction "2_2") (pintype "passive"))
      (node (ref "R20") (pin "1") (pinfunction "1_1") (pintype "passive"))
    )
    (net (code "40") (name "Net-(CASE2-Pad9)") (class "Default")
      (node (ref "CASE2") (pin "9") (pinfunction "9_9") (pintype "passive"))
      (node (ref "R15") (pin "2") (pinfunction "2_2") (pintype "passive"))
      (node (ref "R21") (pin "1") (pinfunction "1_1") (pintype "passive"))
    )
    (net (code "41") (name "Net-(CASE2-Pad11)") (class "Default")
      (node (ref "CASE2") (pin "11") (pinfunction "11_11") (pintype "passive"))
      (node (ref "R16") (pin "2") (pinfunction "2_2") (pintype "passive"))
      (node (ref "R22") (pin "1") (pinfunction "1_1") (pintype "passive"))
    )
    (net (code "42") (name "Net-(CASE2B-1)") (class "Default")
      (node (ref "CASE2") (pin "13") (pinfunction "1_13") (pintype "passive"))
      (node (ref "R1") (pin "2") (pinfunction "2_2") (pintype "passive"))
      (node (ref "R6") (pin "1") (pinfunction "1_1") (pintype "passive"))
    )
    (net (code "43") (name "Net-(CASE2B-3)") (class "Default")
      (node (ref "CASE2") (pin "15") (pinfunction "3_15") (pintype "passive"))
      (node (ref "R23") (pin "2") (pinfunction "2_2") (pintype "passive"))
      (node (ref "R25") (pin "1") (pinfunction "1_1") (pintype "passive"))
    )
    (net (code "44") (name "Net-(CASE2B-6)") (class "Default")
      (node (ref "CASE2") (pin "18") (pinfunction "6_18") (pintype "passive"))
      (node (ref "R2") (pin "2") (pinfunction "2_2") (pintype "passive"))
    )
    (net (code "45") (name "Net-(CASE2B-9)") (class "Default")
      (node (ref "CASE2") (pin "21") (pinfunction "9_21") (pintype "passive"))
      (node (ref "R7") (pin "2") (pinfunction "2_2") (pintype "passive"))
    )
    (net (code "46") (name "Net-(CASE2B-12)") (class "Default")
      (node (ref "CASE2") (pin "24") (pinfunction "12_24") (pintype "passive"))
      (node (ref "R8") (pin "2") (pinfunction "2_2") (pintype "passive"))
    )
    (net (code "47") (name "Net-(CASE2C-3)") (class "Default")
      (node (ref "CASE2") (pin "27") (pinfunction "3_27") (pintype "passive"))
      (node (ref "R9") (pin "2") (pinfunction "2_2") (pintype "passive"))
    )
    (net (code "48") (name "Net-(L1-P$2)") (class "Default")
      (node (ref "D1") (pin "A") (pinfunction "A_A") (pintype "passive"))
      (node (ref "D2") (pin "C") (pinfunction "C_C") (pintype "passive"))
      (node (ref "L1") (pin "2") (pinfunction "P$2_2") (pintype "bidirectional"))
      (node (ref "V1") (pin "2") (pinfunction "2_2") (pintype "passive"))
    )
    (net (code "49") (name "Net-(L3-P$1)") (class "Default")
      (node (ref "C21") (pin "1") (pinfunction "1_1") (pintype "passive"))
      (node (ref "L3") (pin "1") (pinfunction "P$1_1") (pintype "bidirectional"))
      (node (ref "U1") (pin "17") (pinfunction "AVDD_17") (pintype "bidirectional"))
    )
    (net (code "50") (name "Net-(LED1-PadA)") (class "Default")
      (node (ref "LED1") (pin "A") (pinfunction "A_A") (pintype "passive"))
      (node (ref "R43") (pin "1") (pinfunction "1_1") (pintype "passive"))
    )
    (net (code "51") (name "Net-(LED3-PadA)") (class "Default")
      (node (ref "LED3") (pin "A") (pinfunction "A_A") (pintype "passive"))
      (node (ref "R24") (pin "1") (pinfunction "1_1") (pintype "passive"))
    )
    (net (code "52") (name "Net-(LED7-PadA)") (class "Default")
      (node (ref "LED7") (pin "A") (pinfunction "A_A") (pintype "passive"))
      (node (ref "R39") (pin "1") (pinfunction "1_1") (pintype "passive"))
    )
    (net (code "53") (name "Net-(R27-Pad1)") (class "Default")
      (node (ref "R27") (pin "1") (pinfunction "1_1") (pintype "passive"))
      (node (ref "TX2") (pin "A") (pinfunction "A_A") (pintype "passive"))
    )
    (net (code "54") (name "Net-(R28-Pad1)") (class "Default")
      (node (ref "R28") (pin "1") (pinfunction "1_1") (pintype "passive"))
      (node (ref "RX2") (pin "A") (pinfunction "A_A") (pintype "passive"))
    )
    (net (code "55") (name "Net-(R81-Pad1)") (class "Default")
      (node (ref "R81") (pin "1") (pinfunction "1_1") (pintype "passive"))
      (node (ref "TX1") (pin "A") (pinfunction "A_A") (pintype "passive"))
    )
    (net (code "56") (name "Net-(R82-Pad1)") (class "Default")
      (node (ref "R82") (pin "1") (pinfunction "1_1") (pintype "passive"))
      (node (ref "RX1") (pin "A") (pinfunction "A_A") (pintype "passive"))
    )
    (net (code "57") (name "Net-(R87-Pad1)") (class "Default")
      (node (ref "R87") (pin "1") (pinfunction "1_1") (pintype "passive"))
      (node (ref "TX") (pin "A") (pinfunction "A_A") (pintype "passive"))
    )
    (net (code "58") (name "Net-(R88-Pad1)") (class "Default")
      (node (ref "R88") (pin "1") (pinfunction "1_1") (pintype "passive"))
      (node (ref "RX") (pin "A") (pinfunction "A_A") (pintype "passive"))
    )
    (net (code "59") (name "Net-(S2-2)") (class "Default")
      (node (ref "C22") (pin "1") (pinfunction "1_1") (pintype "passive"))
      (node (ref "JP9") (pin "1") (pinfunction "1_1") (pintype "passive"))
      (node (ref "R40") (pin "1") (pinfunction "1_1") (pintype "passive"))
      (node (ref "R41") (pin "1") (pinfunction "1_1") (pintype "passive"))
      (node (ref "S2") (pin "3") (pinfunction "2_3") (pintype "passive"))
      (node (ref "SJ1") (pin "2") (pinfunction "2_2") (pintype "passive"))
    )
    (net (code "60") (name "Net-(U1-OSC1{slash}CLKI{slash}CN30{slash}RA2)") (class "Default")
      (node (ref "C23") (pin "1") (pinfunction "1_1") (pintype "passive"))
      (node (ref "U1") (pin "30") (pinfunction "OSC1/CLKI/CN30/RA2_30") (pintype "bidirectional"))
      (node (ref "Y1") (pin "1") (pinfunction "1_1") (pintype "passive"))
    )
    (net (code "61") (name "Net-(U1-OSC2{slash}CLKO{slash}CN29{slash}RA3)") (class "Default")
      (node (ref "C24") (pin "1") (pinfunction "1_1") (pintype "passive"))
      (node (ref "U1") (pin "31") (pinfunction "OSC2/CLKO/CN29/RA3_31") (pintype "bidirectional"))
      (node (ref "Y1") (pin "3") (pinfunction "2_3") (pintype "passive"))
    )
    (net (code "62") (name "Net-(U1-PGEC2{slash}RP11(1){slash}CN15{slash}PMD1{slash}RB11*)") (class "Default")
      (node (ref "JP9") (pin "5") (pinfunction "5_5") (pintype "passive"))
      (node (ref "U1") (pin "9") (pinfunction "PGEC2/RP11(1)/CN15/PMD1/RB11*_9") (pintype "bidirectional"))
    )
    (net (code "63") (name "Net-(U1-PGED2{slash}EMCD2{slash}RP10(1){slash}CN16{slash}PMD2{slash}RB10*)") (class "Default")
      (node (ref "JP9") (pin "4") (pinfunction "4_4") (pintype "passive"))
      (node (ref "U1") (pin "8") (pinfunction "PGED2/EMCD2/RP10(1)/CN16/PMD2/RB10*_8") (pintype "bidirectional"))
    )
    (net (code "64") (name "Net-(U1-SDA1{slash}RP9{slash}CN21{slash}PMD3{slash}RB9*)") (class "Default")
      (node (ref "R39") (pin "2") (pinfunction "2_2") (pintype "passive"))
      (node (ref "U1") (pin "1") (pinfunction "SDA1/RP9/CN21/PMD3/RB9*_1") (pintype "bidirectional"))
    )
    (net (code "65") (name "Net-(U1-~{MCLR}*)") (class "Default")
      (node (ref "R41") (pin "2") (pinfunction "2_2") (pintype "passive"))
      (node (ref "U1") (pin "18") (pinfunction "~{MCLR}*_18") (pintype "bidirectional"))
    )
    (net (code "66") (name "Net-(U2-A)") (class "Default")
      (node (ref "R7") (pin "1") (pinfunction "1_1") (pintype "passive"))
      (node (ref "U2") (pin "1") (pinfunction "A_1") (pintype "bidirectional"))
    )
    (net (code "67") (name "Net-(U3-A)") (class "Default")
      (node (ref "R8") (pin "1") (pinfunction "1_1") (pintype "passive"))
      (node (ref "U3") (pin "1") (pinfunction "A_1") (pintype "bidirectional"))
    )
    (net (code "68") (name "Net-(U5-A)") (class "Default")
      (node (ref "R9") (pin "1") (pinfunction "1_1") (pintype "passive"))
      (node (ref "U5") (pin "1") (pinfunction "A_1") (pintype "bidirectional"))
    )
    (net (code "69") (name "Net-(U6-A)") (class "Default")
      (node (ref "R2") (pin "1") (pinfunction "1_1") (pintype "passive"))
      (node (ref "U6") (pin "1") (pinfunction "A_1") (pintype "bidirectional"))
    )
    (net (code "70") (name "Net-(U8-RXLED)") (class "Default")
      (node (ref "RX") (pin "C") (pinfunction "C_C") (pintype "passive"))
      (node (ref "U8") (pin "22") (pinfunction "RXLED_22") (pintype "bidirectional"))
    )
    (net (code "71") (name "Net-(U8-TXLED)") (class "Default")
      (node (ref "TX") (pin "C") (pinfunction "C_C") (pintype "passive"))
      (node (ref "U8") (pin "23") (pinfunction "TXLED_23") (pintype "bidirectional"))
    )
    (net (code "72") (name "Net-(U8-USBDM)") (class "Default")
      (node (ref "JP1") (pin "2") (pinfunction "2_2") (pintype "passive"))
      (node (ref "U8") (pin "16") (pinfunction "USBDM_16") (pintype "bidirectional"))
    )
    (net (code "73") (name "Net-(U8-USBDP)") (class "Default")
      (node (ref "JP1") (pin "1") (pinfunction "1_1") (pintype "passive"))
      (node (ref "U8") (pin "15") (pinfunction "USBDP_15") (pintype "bidirectional"))
    )
    (net (code "74") (name "Net-(U9-~{RST})") (class "Default")
      (node (ref "SJ1") (pin "1") (pinfunction "1_1") (pintype "passive"))
      (node (ref "U9") (pin "1") (pinfunction "~{RST}_1") (pintype "bidirectional"))
    )
    (net (code "75") (name "Net-(U11--IN)") (class "Default")
      (node (ref "R26") (pin "2") (pinfunction "2_2") (pintype "passive"))
      (node (ref "U11") (pin "1") (pinfunction "OUT_1") (pintype "output"))
      (node (ref "U11") (pin "4") (pinfunction "-IN_4") (pintype "input"))
    )
    (net (code "76") (name "Net-(U14-1A)") (class "Default")
      (node (ref "U14") (pin "2") (pinfunction "1A_2") (pintype "bidirectional"))
      (node (ref "U8") (pin "1") (pinfunction "TXD_1") (pintype "output"))
    )
    (net (code "77") (name "Net-(U14-2OE)") (class "Default")
      (node (ref "R38") (pin "1") (pinfunction "1_1") (pintype "passive"))
      (node (ref "U14") (pin "7") (pinfunction "2OE_7") (pintype "bidirectional"))
    )
    (net (code "78") (name "Net-(U14-2Y)") (class "Default")
      (node (ref "U14") (pin "3") (pinfunction "2Y_3") (pintype "bidirectional"))
      (node (ref "U8") (pin "5") (pinfunction "RXD_5") (pintype "input"))
    )
    (net (code "79") (name "unconnected-(CASE2C-5-Pad29)") (class "Default")
      (node (ref "CASE2") (pin "29") (pinfunction "5_29") (pintype "passive"))
    )
    (net (code "80") (name "unconnected-(CASE2C-6-Pad30)") (class "Default")
      (node (ref "CASE2") (pin "30") (pinfunction "6_30") (pintype "passive"))
    )
    (net (code "81") (name "unconnected-(CASE2C-7-Pad31)") (class "Default")
      (node (ref "CASE2") (pin "31") (pinfunction "7_31") (pintype "passive"))
    )
    (net (code "82") (name "unconnected-(CASE2C-8-Pad32)") (class "Default")
      (node (ref "CASE2") (pin "32") (pinfunction "8_32") (pintype "passive"))
    )
    (net (code "83") (name "unconnected-(CASE2C-9-Pad33)") (class "Default")
      (node (ref "CASE2") (pin "33") (pinfunction "9_33") (pintype "passive"))
    )
    (net (code "84") (name "unconnected-(CASE2C-12-Pad36)") (class "Default")
      (node (ref "CASE2") (pin "36") (pinfunction "12_36") (pintype "passive"))
    )
    (net (code "85") (name "unconnected-(CASE2D-8-Pad44)") (class "Default")
      (node (ref "CASE2") (pin "44") (pinfunction "8_44") (pintype "passive"))
    )
    (net (code "86") (name "unconnected-(CASE2D-9-Pad45)") (class "Default")
      (node (ref "CASE2") (pin "45") (pinfunction "9_45") (pintype "passive"))
    )
    (net (code "87") (name "unconnected-(CASE2D-10-Pad46)") (class "Default")
      (node (ref "CASE2") (pin "46") (pinfunction "10_46") (pintype "passive"))
    )
    (net (code "88") (name "unconnected-(CASE2D-11-Pad47)") (class "Default")
      (node (ref "CASE2") (pin "47") (pinfunction "11_47") (pintype "passive"))
    )
    (net (code "89") (name "unconnected-(CASE2D-12-Pad48)") (class "Default")
      (node (ref "CASE2") (pin "48") (pinfunction "12_48") (pintype "passive"))
    )
    (net (code "90") (name "unconnected-(U1-*RP19(1){slash}CN28{slash}PMBE{slash}RC3-Pad36)") (class "Default")
      (node (ref "U1") (pin "36") (pinfunction "*RP19(1)/CN28/PMBE/RC3_36") (pintype "bidirectional"))
    )
    (net (code "91") (name "unconnected-(U1-*TDI{slash}PMA9{slash}RA9-Pad35)") (class "Default")
      (node (ref "U1") (pin "35") (pinfunction "*TDI/PMA9/RA9_35") (pintype "bidirectional"))
    )
    (net (code "92") (name "unconnected-(U1-*TDO{slash}PMA8{slash}RA8-Pad32)") (class "Default")
      (node (ref "U1") (pin "32") (pinfunction "*TDO/PMA8/RA8_32") (pintype "bidirectional"))
    )
    (net (code "93") (name "unconnected-(U1-AN8{slash}CVREF{slash}RP18(1){slash}PMA2{slash}CN10{slash}RC2-Pad27)") (class "Default")
      (node (ref "U1") (pin "27") (pinfunction "AN8/CVREF/RP18(1)/PMA2/CN10/RC2_27") (pintype "bidirectional"))
    )
    (net (code "94") (name "unconnected-(U1-AN9{slash}DAC1LN{slash}RP15(1){slash}CN11{slash}PMCS1{slash}RB15*-Pad15)") (class "Default")
      (node (ref "U1") (pin "15") (pinfunction "AN9/DAC1LN/RP15(1)/CN11/PMCS1/RB15*_15") (pintype "bidirectional"))
    )
    (net (code "95") (name "unconnected-(U1-AN10{slash}DAC1LP{slash}RTCC{slash}RP14*-Pad14)") (class "Default")
      (node (ref "U1") (pin "14") (pinfunction "AN10/DAC1LP/RTCC/RP14*_14") (pintype "bidirectional"))
    )
    (net (code "96") (name "unconnected-(U1-AN11{slash}DAC1RN{slash}RP13(1){slash}CN13{slash}PMRD{slash}RB13-Pad11)") (class "Default")
      (node (ref "U1") (pin "11") (pinfunction "AN11/DAC1RN/RP13(1)/CN13/PMRD/RB13_11") (pintype "bidirectional"))
    )
    (net (code "97") (name "unconnected-(U1-SOSCI{slash}RP4(1){slash}CN1{slash}RB4-Pad33)") (class "Default")
      (node (ref "U1") (pin "33") (pinfunction "SOSCI/RP4(1)/CN1/RB4_33") (pintype "bidirectional"))
    )
    (net (code "98") (name "unconnected-(U1-SOSCO{slash}T1CK{slash}CN0{slash}RA4-Pad34)") (class "Default")
      (node (ref "U1") (pin "34") (pinfunction "SOSCO/T1CK/CN0/RA4_34") (pintype "bidirectional"))
    )
    (net (code "99") (name "unconnected-(U1-TCK{slash}PMA7{slash}RA7*-Pad13)") (class "Default")
      (node (ref "U1") (pin "13") (pinfunction "TCK/PMA7/RA7*_13") (pintype "bidirectional"))
    )
    (net (code "100") (name "unconnected-(U1-TMS{slash}PMA10{slash}RA10*-Pad12)") (class "Default")
      (node (ref "U1") (pin "12") (pinfunction "TMS/PMA10/RA10*_12") (pintype "bidirectional"))
    )
    (net (code "101") (name "unconnected-(U8-CTS-Pad11)") (class "Default")
      (node (ref "U8") (pin "11") (pinfunction "CTS_11") (pintype "bidirectional"))
    )
    (net (code "102") (name "unconnected-(U8-DTR-Pad2)") (class "Default")
      (node (ref "U8") (pin "2") (pinfunction "DTR_2") (pintype "bidirectional"))
    )
    (net (code "103") (name "unconnected-(U8-RTS-Pad3)") (class "Default")
      (node (ref "U8") (pin "3") (pinfunction "RTS_3") (pintype "bidirectional"))
    )
    (net (code "104") (name "unconnected-(U9-~{MR}-Pad3)") (class "Default")
      (node (ref "U9") (pin "3") (pinfunction "~{MR}_3") (pintype "bidirectional"))
    )
  )
)
